# lcd-i2c.net
KiCad netlist of a schematic drawn in EAGLE
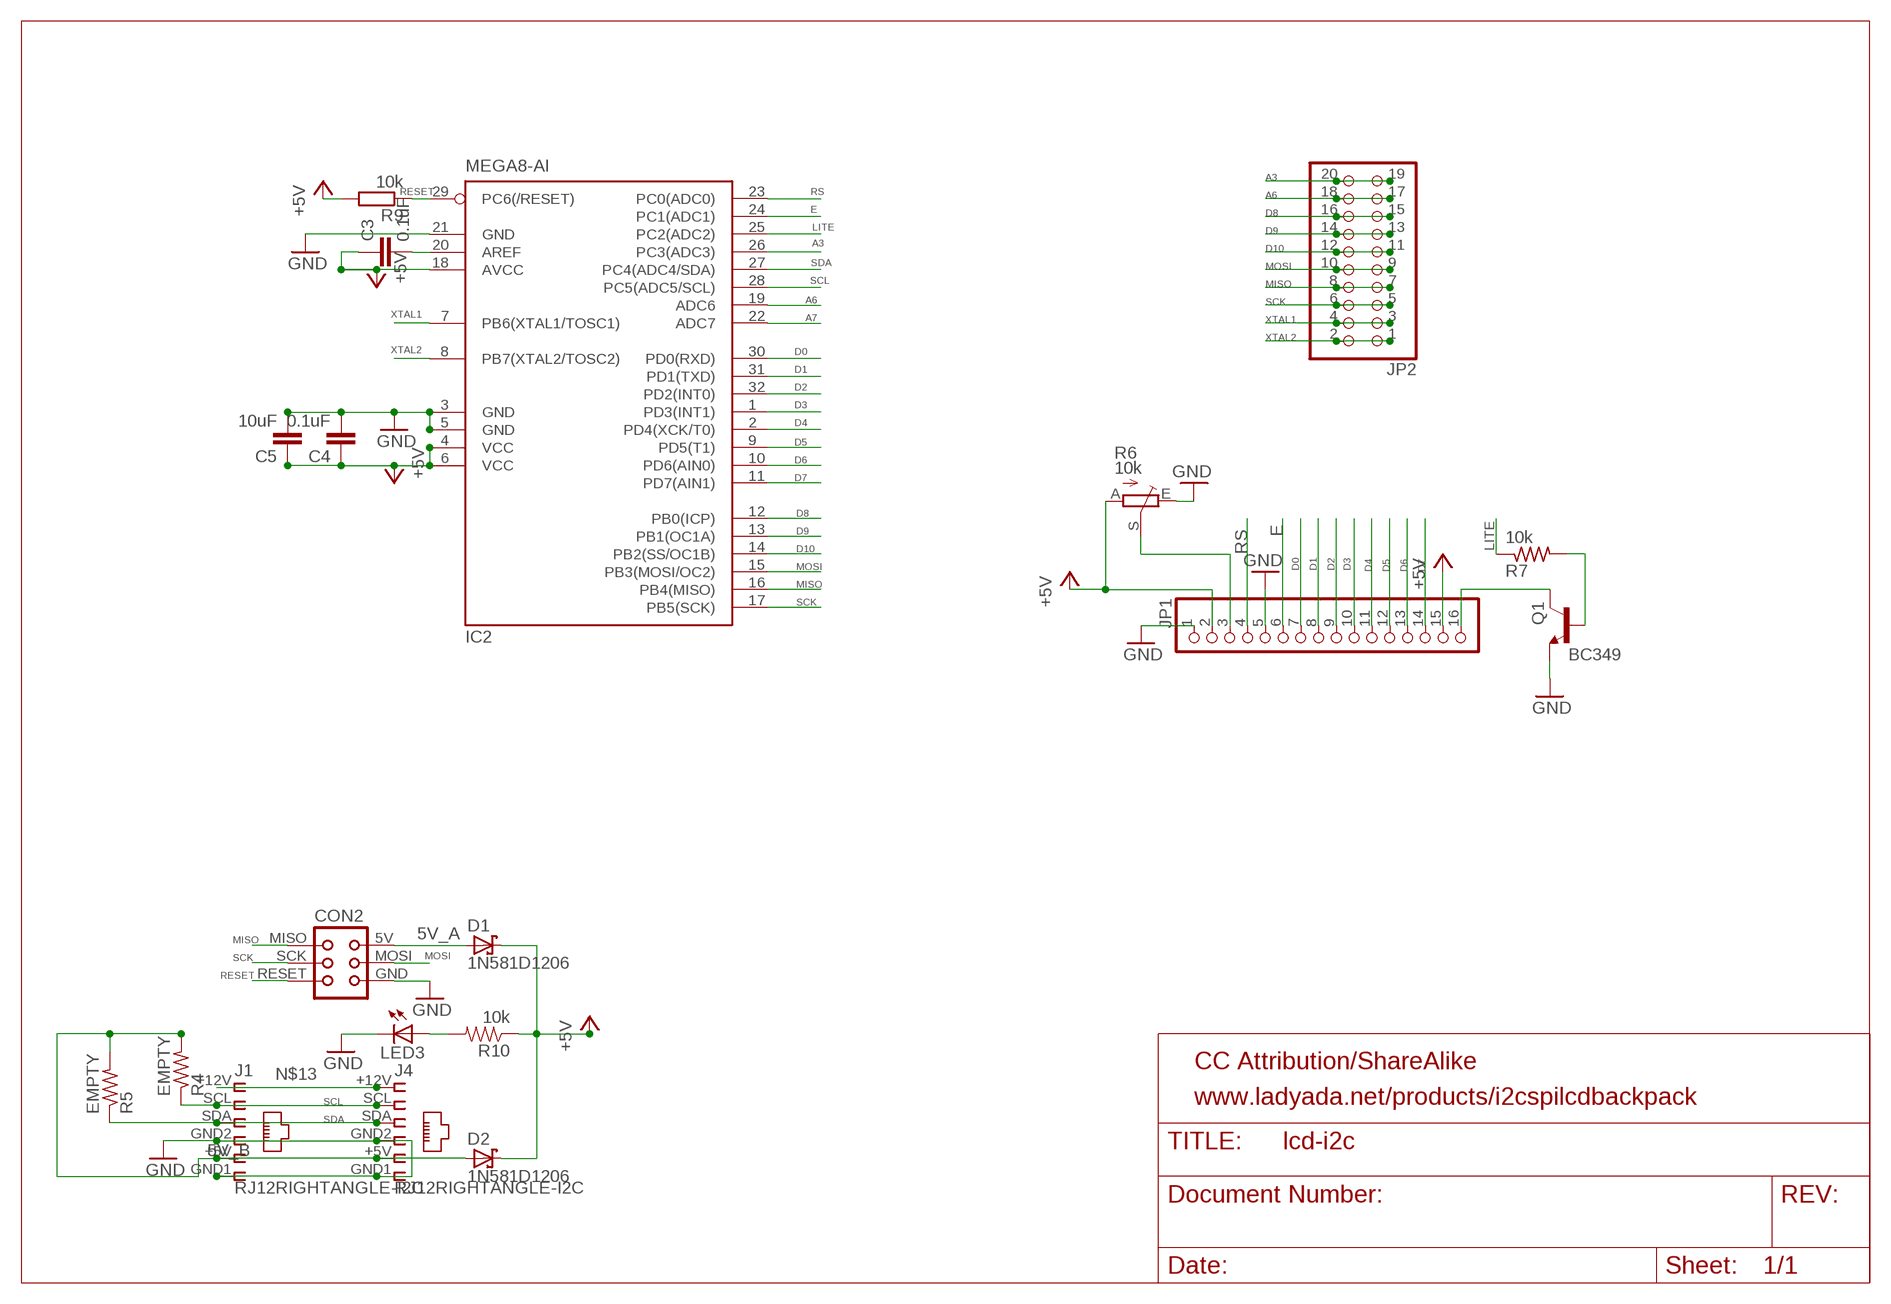
[diagram p0: schematic, sheet 1]

(export (version "E")
  (design (tool "Eeschema 10.0.6"))
  (components
    (comp (ref "C3")
      (value "0.1uF")
      (footprint "eagle-import:C1206")
      (libsource (lib "eagle-import") (part "C-EUC1206"))
    )
    (comp (ref "C4")
      (value "0.1uF")
      (footprint "eagle-import:C1206")
      (libsource (lib "eagle-import") (part "C-EUC1206"))
    )
    (comp (ref "C5")
      (value "10uF")
      (footprint "eagle-import:C1206")
      (libsource (lib "eagle-import") (part "C-EUC1206"))
    )
    (comp (ref "CON2")
      (value "TINYISPTAG")
      (footprint "eagle-import:TC2030-MCP")
      (libsource (lib "eagle-import") (part "TINYISPTAG"))
    )
    (comp (ref "D1")
      (value "1N581D1206")
      (footprint "eagle-import:LED-1206")
      (libsource (lib "eagle-import") (part "1N581D1206"))
    )
    (comp (ref "D2")
      (value "1N581D1206")
      (footprint "eagle-import:LED-1206")
      (libsource (lib "eagle-import") (part "1N581D1206"))
    )
    (comp (ref "IC2")
      (value "MEGA8-AI")
      (footprint "eagle-import:TQFP32-08")
      (fields (field (name "MPN") "ATMEGA8-16AU"))
      (libsource (lib "eagle-import") (part "MEGA8-AI"))
    )
    (comp (ref "J1")
      (value "RJ12RIGHTANGLE-I2C")
      (footprint "eagle-import:RJ12-RIGHTANGLE-I2C")
      (libsource (lib "eagle-import") (part "RJ12RIGHTANGLE-I2C"))
    )
    (comp (ref "J4")
      (value "RJ12RIGHTANGLE-I2C")
      (footprint "eagle-import:RJ12-RIGHTANGLE-I2C")
      (libsource (lib "eagle-import") (part "RJ12RIGHTANGLE-I2C"))
    )
    (comp (ref "JP1")
      (value "PINHD-1X16")
      (footprint "eagle-import:1X16")
      (libsource (lib "eagle-import") (part "PINHD-1X16"))
    )
    (comp (ref "JP2")
      (value "PINHD-2X10")
      (footprint "eagle-import:2X10")
      (libsource (lib "eagle-import") (part "PINHD-2X10"))
    )
    (comp (ref "LED3")
      (value "LEDCHIP-LED0603")
      (footprint "eagle-import:CHIP-LED0603")
      (libsource (lib "eagle-import") (part "LEDCHIP-LED0603"))
    )
    (comp (ref "Q1")
      (value "BC349")
      (footprint "eagle-import:TO92-EBC")
      (libsource (lib "eagle-import") (part "-NPN-TO92-EBCBC317"))
    )
    (comp (ref "R4")
      (value "EMPTY")
      (footprint "eagle-import:M1206")
      (libsource (lib "eagle-import") (part "R-US_M1206"))
    )
    (comp (ref "R5")
      (value "EMPTY")
      (footprint "eagle-import:M1206")
      (libsource (lib "eagle-import") (part "R-US_M1206"))
    )
    (comp (ref "R6")
      (value "10k")
      (footprint "eagle-import:CA6V")
      (libsource (lib "eagle-import") (part "TRIM_EU-CA6V"))
    )
    (comp (ref "R7")
      (value "10k")
      (footprint "eagle-import:M1206")
      (libsource (lib "eagle-import") (part "R-US_M1206"))
    )
    (comp (ref "R9")
      (value "10k")
      (footprint "eagle-import:M1206")
      (libsource (lib "eagle-import") (part "R-EU_M1206"))
    )
    (comp (ref "R10")
      (value "10k")
      (footprint "eagle-import:0603-RES")
      (libsource (lib "eagle-import") (part "RESISTOR0603-RES"))
    )
  )
  (nets
    (net (code "1") (name "+5V") (class "Default")
      (node (ref "C3") (pin "1") (pinfunction "1_1") (pintype "passive"))
      (node (ref "C4") (pin "1") (pinfunction "1_1") (pintype "passive"))
      (node (ref "C5") (pin "1") (pinfunction "1_1") (pintype "passive"))
      (node (ref "D1") (pin "C") (pinfunction "C_C") (pintype "passive"))
      (node (ref "D2") (pin "C") (pinfunction "C_C") (pintype "passive"))
      (node (ref "IC2") (pin "18") (pinfunction "AVCC_18") (pintype "power_in"))
      (node (ref "IC2") (pin "4") (pinfunction "VCC_4") (pintype "power_in"))
      (node (ref "IC2") (pin "6") (pinfunction "VCC_6") (pintype "power_in"))
      (node (ref "JP1") (pin "15") (pinfunction "15_15") (pintype "passive"))
      (node (ref "JP1") (pin "2") (pinfunction "2_2") (pintype "passive"))
      (node (ref "R10") (pin "1") (pinfunction "1_1") (pintype "passive"))
      (node (ref "R6") (pin "A") (pinfunction "A_A") (pintype "passive"))
      (node (ref "R9") (pin "2") (pinfunction "2_2") (pintype "passive"))
    )
    (net (code "2") (name "/5V_A") (class "Default")
      (node (ref "CON2") (pin "5V") (pinfunction "VCC_5V") (pintype "passive"))
      (node (ref "D1") (pin "A") (pinfunction "A_A") (pintype "passive"))
    )
    (net (code "3") (name "/5V_B") (class "Default")
      (node (ref "D2") (pin "A") (pinfunction "A_A") (pintype "passive"))
      (node (ref "J1") (pin "+5V") (pinfunction "5_+5V") (pintype "bidirectional"))
      (node (ref "J4") (pin "+5V") (pinfunction "5_+5V") (pintype "bidirectional"))
      (node (ref "R4") (pin "2") (pinfunction "2_2") (pintype "passive"))
      (node (ref "R5") (pin "2") (pinfunction "2_2") (pintype "passive"))
    )
    (net (code "4") (name "/A3") (class "Default")
      (node (ref "IC2") (pin "26") (pinfunction "PC3(ADC3)_26") (pintype "bidirectional"))
      (node (ref "JP2") (pin "19") (pinfunction "19_19") (pintype "passive"))
      (node (ref "JP2") (pin "20") (pinfunction "20_20") (pintype "passive"))
    )
    (net (code "5") (name "/A6") (class "Default")
      (node (ref "IC2") (pin "19") (pinfunction "ADC6_19") (pintype "bidirectional"))
      (node (ref "JP2") (pin "17") (pinfunction "17_17") (pintype "passive"))
      (node (ref "JP2") (pin "18") (pinfunction "18_18") (pintype "passive"))
    )
    (net (code "6") (name "/A7") (class "Default")
      (node (ref "IC2") (pin "22") (pinfunction "ADC7_22") (pintype "bidirectional"))
    )
    (net (code "7") (name "/D0") (class "Default")
      (node (ref "IC2") (pin "30") (pinfunction "PD0(RXD)_30") (pintype "bidirectional"))
      (node (ref "JP1") (pin "7") (pinfunction "7_7") (pintype "passive"))
    )
    (net (code "8") (name "/D1") (class "Default")
      (node (ref "IC2") (pin "31") (pinfunction "PD1(TXD)_31") (pintype "bidirectional"))
      (node (ref "JP1") (pin "8") (pinfunction "8_8") (pintype "passive"))
    )
    (net (code "9") (name "/D2") (class "Default")
      (node (ref "IC2") (pin "32") (pinfunction "PD2(INT0)_32") (pintype "bidirectional"))
      (node (ref "JP1") (pin "9") (pinfunction "9_9") (pintype "passive"))
    )
    (net (code "10") (name "/D3") (class "Default")
      (node (ref "IC2") (pin "1") (pinfunction "PD3(INT1)_1") (pintype "bidirectional"))
      (node (ref "JP1") (pin "10") (pinfunction "10_10") (pintype "passive"))
    )
    (net (code "11") (name "/D4") (class "Default")
      (node (ref "IC2") (pin "2") (pinfunction "PD4(XCK/T0)_2") (pintype "bidirectional"))
      (node (ref "JP1") (pin "11") (pinfunction "11_11") (pintype "passive"))
    )
    (net (code "12") (name "/D5") (class "Default")
      (node (ref "IC2") (pin "9") (pinfunction "PD5(T1)_9") (pintype "bidirectional"))
      (node (ref "JP1") (pin "12") (pinfunction "12_12") (pintype "passive"))
    )
    (net (code "13") (name "/D6") (class "Default")
      (node (ref "IC2") (pin "10") (pinfunction "PD6(AIN0)_10") (pintype "bidirectional"))
      (node (ref "JP1") (pin "13") (pinfunction "13_13") (pintype "passive"))
    )
    (net (code "14") (name "/D7") (class "Default")
      (node (ref "IC2") (pin "11") (pinfunction "PD7(AIN1)_11") (pintype "bidirectional"))
      (node (ref "JP1") (pin "14") (pinfunction "14_14") (pintype "passive"))
    )
    (net (code "15") (name "/D8") (class "Default")
      (node (ref "IC2") (pin "12") (pinfunction "PB0(ICP)_12") (pintype "bidirectional"))
      (node (ref "JP2") (pin "15") (pinfunction "15_15") (pintype "passive"))
      (node (ref "JP2") (pin "16") (pinfunction "16_16") (pintype "passive"))
    )
    (net (code "16") (name "/D9") (class "Default")
      (node (ref "IC2") (pin "13") (pinfunction "PB1(OC1A)_13") (pintype "bidirectional"))
      (node (ref "JP2") (pin "13") (pinfunction "13_13") (pintype "passive"))
      (node (ref "JP2") (pin "14") (pinfunction "14_14") (pintype "passive"))
    )
    (net (code "17") (name "/D10") (class "Default")
      (node (ref "IC2") (pin "14") (pinfunction "PB2(SS/OC1B)_14") (pintype "bidirectional"))
      (node (ref "JP2") (pin "11") (pinfunction "11_11") (pintype "passive"))
      (node (ref "JP2") (pin "12") (pinfunction "12_12") (pintype "passive"))
    )
    (net (code "18") (name "/E") (class "Default")
      (node (ref "IC2") (pin "24") (pinfunction "PC1(ADC1)_24") (pintype "bidirectional"))
      (node (ref "JP1") (pin "6") (pinfunction "6_6") (pintype "passive"))
    )
    (net (code "19") (name "/LITE") (class "Default")
      (node (ref "IC2") (pin "25") (pinfunction "PC2(ADC2)_25") (pintype "bidirectional"))
      (node (ref "R7") (pin "1") (pinfunction "1_1") (pintype "passive"))
    )
    (net (code "20") (name "/MISO") (class "Default")
      (node (ref "CON2") (pin "MISO") (pinfunction "MISO_MISO") (pintype "passive"))
      (node (ref "IC2") (pin "16") (pinfunction "PB4(MISO)_16") (pintype "bidirectional"))
      (node (ref "JP2") (pin "7") (pinfunction "7_7") (pintype "passive"))
      (node (ref "JP2") (pin "8") (pinfunction "8_8") (pintype "passive"))
    )
    (net (code "21") (name "/MOSI") (class "Default")
      (node (ref "CON2") (pin "MOSI") (pinfunction "MOSI_MOSI") (pintype "passive"))
      (node (ref "IC2") (pin "15") (pinfunction "PB3(MOSI/OC2)_15") (pintype "bidirectional"))
      (node (ref "JP2") (pin "10") (pinfunction "10_10") (pintype "passive"))
      (node (ref "JP2") (pin "9") (pinfunction "9_9") (pintype "passive"))
    )
    (net (code "22") (name "/N$13") (class "Default")
      (node (ref "J1") (pin "+12V") (pinfunction "1_+12V") (pintype "bidirectional"))
      (node (ref "J4") (pin "+12V") (pinfunction "1_+12V") (pintype "bidirectional"))
    )
    (net (code "23") (name "/RESET") (class "Default")
      (node (ref "CON2") (pin "RESET") (pinfunction "RESET_RESET") (pintype "passive"))
      (node (ref "IC2") (pin "29") (pinfunction "PC6(/RESET)_29") (pintype "bidirectional"))
      (node (ref "R9") (pin "1") (pinfunction "1_1") (pintype "passive"))
    )
    (net (code "24") (name "/RS") (class "Default")
      (node (ref "IC2") (pin "23") (pinfunction "PC0(ADC0)_23") (pintype "bidirectional"))
      (node (ref "JP1") (pin "4") (pinfunction "4_4") (pintype "passive"))
    )
    (net (code "25") (name "/SCK") (class "Default")
      (node (ref "CON2") (pin "SCK") (pinfunction "SCK_SCK") (pintype "passive"))
      (node (ref "IC2") (pin "17") (pinfunction "PB5(SCK)_17") (pintype "bidirectional"))
      (node (ref "JP2") (pin "5") (pinfunction "5_5") (pintype "passive"))
      (node (ref "JP2") (pin "6") (pinfunction "6_6") (pintype "passive"))
    )
    (net (code "26") (name "/SCL") (class "Default")
      (node (ref "IC2") (pin "28") (pinfunction "PC5(ADC5/SCL)_28") (pintype "bidirectional"))
      (node (ref "J1") (pin "SCL") (pinfunction "2_SCL") (pintype "bidirectional"))
      (node (ref "J4") (pin "SCL") (pinfunction "2_SCL") (pintype "bidirectional"))
      (node (ref "R4") (pin "1") (pinfunction "1_1") (pintype "passive"))
    )
    (net (code "27") (name "/SDA") (class "Default")
      (node (ref "IC2") (pin "27") (pinfunction "PC4(ADC4/SDA)_27") (pintype "bidirectional"))
      (node (ref "J1") (pin "SDA") (pinfunction "3_SDA") (pintype "bidirectional"))
      (node (ref "J4") (pin "SDA") (pinfunction "3_SDA") (pintype "bidirectional"))
      (node (ref "R5") (pin "1") (pinfunction "1_1") (pintype "passive"))
    )
    (net (code "28") (name "/XTAL1") (class "Default")
      (node (ref "IC2") (pin "7") (pinfunction "PB6(XTAL1/TOSC1)_7") (pintype "bidirectional"))
      (node (ref "JP2") (pin "3") (pinfunction "3_3") (pintype "passive"))
      (node (ref "JP2") (pin "4") (pinfunction "4_4") (pintype "passive"))
    )
    (net (code "29") (name "/XTAL2") (class "Default")
      (node (ref "IC2") (pin "8") (pinfunction "PB7(XTAL2/TOSC2)_8") (pintype "bidirectional"))
      (node (ref "JP2") (pin "1") (pinfunction "1_1") (pintype "passive"))
      (node (ref "JP2") (pin "2") (pinfunction "2_2") (pintype "passive"))
    )
    (net (code "30") (name "GND") (class "Default")
      (node (ref "C4") (pin "2") (pinfunction "2_2") (pintype "passive"))
      (node (ref "C5") (pin "2") (pinfunction "2_2") (pintype "passive"))
      (node (ref "CON2") (pin "GND") (pinfunction "GND_GND") (pintype "passive"))
      (node (ref "IC2") (pin "21") (pinfunction "GND_21") (pintype "power_in"))
      (node (ref "IC2") (pin "3") (pinfunction "GND_3") (pintype "power_in"))
      (node (ref "IC2") (pin "5") (pinfunction "GND_5") (pintype "power_in"))
      (node (ref "J1") (pin "GND1") (pinfunction "6_GND1") (pintype "bidirectional"))
      (node (ref "J1") (pin "GND2") (pinfunction "4_GND2") (pintype "bidirectional"))
      (node (ref "J4") (pin "GND1") (pinfunction "6_GND1") (pintype "bidirectional"))
      (node (ref "J4") (pin "GND2") (pinfunction "4_GND2") (pintype "bidirectional"))
      (node (ref "JP1") (pin "1") (pinfunction "1_1") (pintype "passive"))
      (node (ref "JP1") (pin "5") (pinfunction "5_5") (pintype "passive"))
      (node (ref "LED3") (pin "C") (pinfunction "C_C") (pintype "passive"))
      (node (ref "Q1") (pin "E") (pinfunction "E_E") (pintype "passive"))
      (node (ref "R6") (pin "E") (pinfunction "E_E") (pintype "passive"))
    )
    (net (code "31") (name "Net-(IC2-AREF)") (class "Default")
      (node (ref "C3") (pin "2") (pinfunction "2_2") (pintype "passive"))
      (node (ref "IC2") (pin "20") (pinfunction "AREF_20") (pintype "passive"))
    )
    (net (code "32") (name "Net-(JP1-Pad3)") (class "Default")
      (node (ref "JP1") (pin "3") (pinfunction "3_3") (pintype "passive"))
      (node (ref "R6") (pin "S") (pinfunction "S_S") (pintype "passive"))
    )
    (net (code "33") (name "Net-(JP1-Pad16)") (class "Default")
      (node (ref "JP1") (pin "16") (pinfunction "16_16") (pintype "passive"))
      (node (ref "Q1") (pin "C") (pinfunction "C_C") (pintype "passive"))
    )
    (net (code "34") (name "Net-(LED3-PadA)") (class "Default")
      (node (ref "LED3") (pin "A") (pinfunction "A_A") (pintype "passive"))
      (node (ref "R10") (pin "2") (pinfunction "2_2") (pintype "passive"))
    )
    (net (code "35") (name "Net-(Q1-PadB)") (class "Default")
      (node (ref "Q1") (pin "B") (pinfunction "B_B") (pintype "passive"))
      (node (ref "R7") (pin "2") (pinfunction "2_2") (pintype "passive"))
    )
  )
)
